# DisclosureDrawings.net
KiCad netlist of a schematic drawn in EAGLE
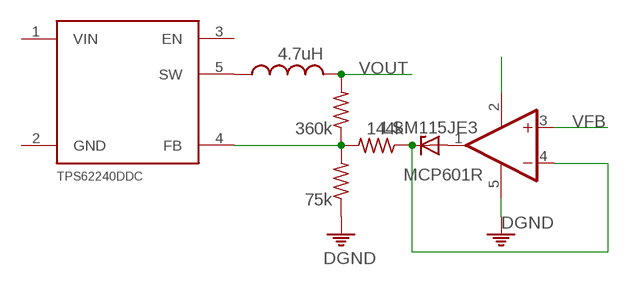
[diagram p0: schematic, sheet 1]

(export (version "E")
  (design (tool "Eeschema 10.0.6"))
  (components
    (comp (ref "D9")
      (value "LSM115JE3")
      (footprint "eagle-import:DO214BA")
      (libsource (lib "eagle-import") (part "LSM115JE3"))
    )
    (comp (ref "L19")
      (value "4.7uH")
      (footprint "eagle-import:L1008_2520METRIC")
      (libsource (lib "eagle-import") (part "LQM2HP_G0"))
    )
    (comp (ref "R105")
      (value "144k")
      (footprint "eagle-import:R0603")
      (libsource (lib "eagle-import") (part "R-US_R0603"))
    )
    (comp (ref "R107")
      (value "360k")
      (footprint "eagle-import:R0603")
      (libsource (lib "eagle-import") (part "R-US_R0603"))
    )
    (comp (ref "R108")
      (value "75k")
      (footprint "eagle-import:R0603")
      (libsource (lib "eagle-import") (part "R-US_R0603"))
    )
    (comp (ref "U25")
      (value "MCP601R")
      (footprint "eagle-import:SOT23-5")
      (libsource (lib "eagle-import") (part "MCP601R"))
    )
    (comp (ref "U43")
      (value "TPS62240DDC")
      (footprint "eagle-import:SOT23-5")
      (libsource (lib "eagle-import") (part "TPS62240DDC"))
    )
  )
  (nets
    (net (code "1") (name "/VFB") (class "Default")
      (node (ref "U25") (pin "3") (pinfunction "+IN_3") (pintype "input"))
    )
    (net (code "2") (name "/VOUT") (class "Default")
      (node (ref "L19") (pin "2") (pinfunction "2_2") (pintype "passive"))
      (node (ref "R107") (pin "2") (pinfunction "2_2") (pintype "passive"))
    )
    (net (code "3") (name "DGND") (class "Default")
      (node (ref "R108") (pin "1") (pinfunction "1_1") (pintype "passive"))
      (node (ref "U25") (pin "5") (pinfunction "V-_5") (pintype "power_in"))
    )
    (net (code "4") (name "Net-(U25--IN)") (class "Default")
      (node (ref "D9") (pin "C") (pinfunction "C_C") (pintype "passive"))
      (node (ref "R105") (pin "1") (pinfunction "1_1") (pintype "passive"))
      (node (ref "U25") (pin "4") (pinfunction "-IN_4") (pintype "input"))
    )
    (net (code "5") (name "Net-(U25-OUT)") (class "Default")
      (node (ref "D9") (pin "A") (pinfunction "A_A") (pintype "passive"))
      (node (ref "U25") (pin "1") (pinfunction "OUT_1") (pintype "output"))
    )
    (net (code "6") (name "Net-(U43-FB)") (class "Default")
      (node (ref "R105") (pin "2") (pinfunction "2_2") (pintype "passive"))
      (node (ref "R107") (pin "1") (pinfunction "1_1") (pintype "passive"))
      (node (ref "R108") (pin "2") (pinfunction "2_2") (pintype "passive"))
      (node (ref "U43") (pin "4") (pinfunction "FB_4") (pintype "bidirectional"))
    )
    (net (code "7") (name "Net-(U43-SW)") (class "Default")
      (node (ref "L19") (pin "1") (pinfunction "1_1") (pintype "passive"))
      (node (ref "U43") (pin "5") (pinfunction "SW_5") (pintype "bidirectional"))
    )
    (net (code "8") (name "unconnected-(U25-V+-Pad2)") (class "Default")
      (node (ref "U25") (pin "2") (pinfunction "V+_2") (pintype "power_in"))
    )
    (net (code "9") (name "unconnected-(U43-EN-Pad3)") (class "Default")
      (node (ref "U43") (pin "3") (pinfunction "EN_3") (pintype "bidirectional"))
    )
    (net (code "10") (name "unconnected-(U43-GND-Pad2)") (class "Default")
      (node (ref "U43") (pin "2") (pinfunction "GND_2") (pintype "bidirectional"))
    )
    (net (code "11") (name "unconnected-(U43-VIN-Pad1)") (class "Default")
      (node (ref "U43") (pin "1") (pinfunction "VIN_1") (pintype "bidirectional"))
    )
  )
)
